# Truss-Power.net
KiCad netlist of a schematic drawn in EAGLE
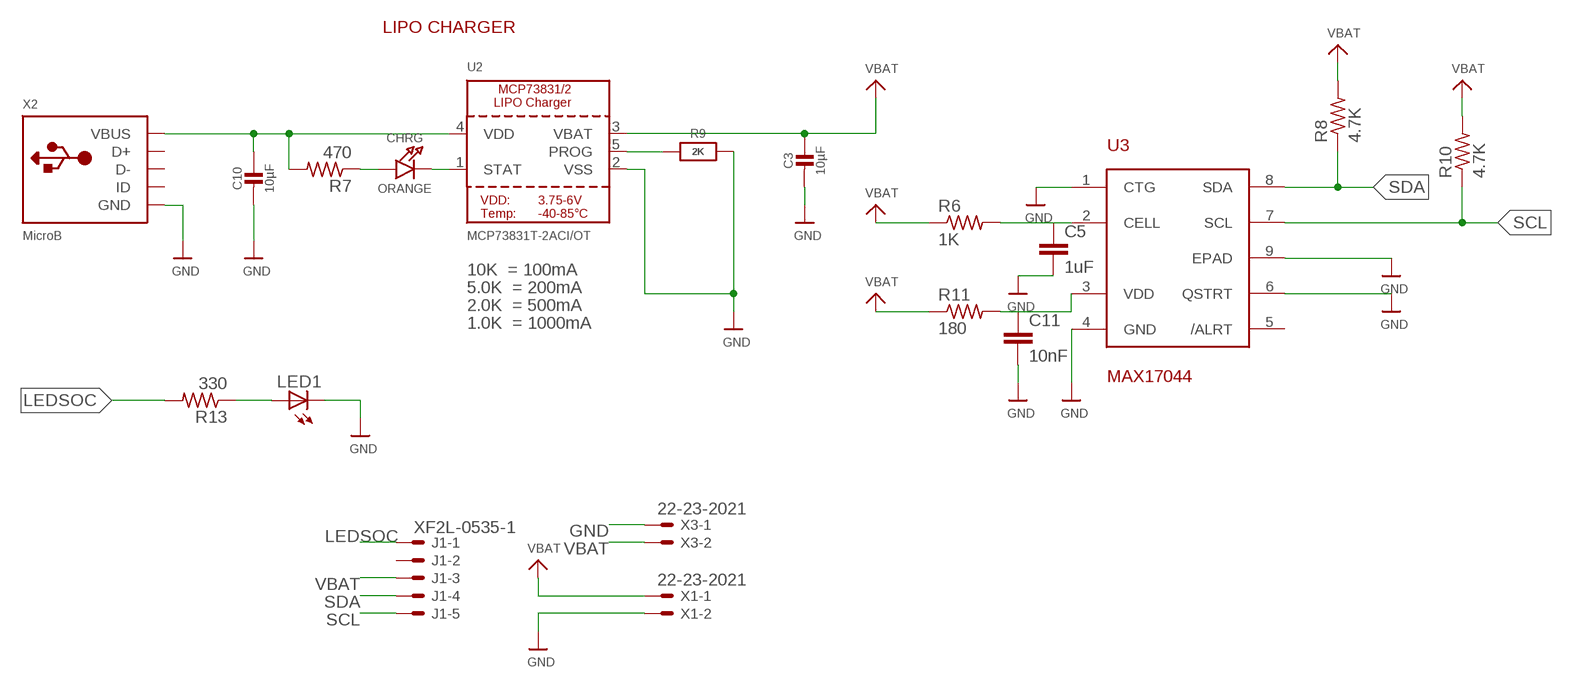
[diagram p0: schematic, sheet 1]

(export (version "E")
  (design (tool "Eeschema 10.0.6"))
  (components
    (comp (ref "C3")
      (value "10µF")
      (footprint "eagle-import:0805-NO")
      (libsource (lib "eagle-import") (part "CAP_CERAMIC0805-NOOUTLINE"))
    )
    (comp (ref "C5")
      (value "1uF")
      (footprint "eagle-import:C0603")
      (libsource (lib "eagle-import") (part "C-EUC0603"))
    )
    (comp (ref "C10")
      (value "10µF")
      (footprint "eagle-import:0805-NO")
      (libsource (lib "eagle-import") (part "CAP_CERAMIC0805-NOOUTLINE"))
    )
    (comp (ref "C11")
      (value "10nF")
      (footprint "eagle-import:C0603")
      (libsource (lib "eagle-import") (part "C-EUC0603"))
    )
    (comp (ref "CHRG")
      (value "ORANGE")
      (footprint "eagle-import:CHIPLED_0805_NOOUTLINE")
      (libsource (lib "eagle-import") (part "LED0805_NOOUTLINE"))
    )
    (comp (ref "J1")
      (value "XF2L-0535-1")
      (footprint "eagle-import:XF2L-0535-1")
      (fields (field (name "MPN") "XF2L-0535-1A"))
      (libsource (lib "eagle-import") (part "XF2-05?35-1L"))
    )
    (comp (ref "LED1")
      (value "LEDCHIP-LED0603")
      (footprint "eagle-import:CHIP-LED0603")
      (libsource (lib "eagle-import") (part "LEDCHIP-LED0603"))
    )
    (comp (ref "R6")
      (value "1K")
      (footprint "eagle-import:R0402")
      (libsource (lib "eagle-import") (part "R-US_R0402"))
    )
    (comp (ref "R7")
      (value "470")
      (footprint "eagle-import:R0402")
      (libsource (lib "eagle-import") (part "R-US_R0402"))
    )
    (comp (ref "R8")
      (value "4.7K")
      (footprint "eagle-import:R0402")
      (libsource (lib "eagle-import") (part "R-US_R0402"))
    )
    (comp (ref "R9")
      (value "2K")
      (footprint "eagle-import:0805-NO")
      (libsource (lib "eagle-import") (part "RESISTOR0805_NOOUTLINE"))
    )
    (comp (ref "R10")
      (value "4.7K")
      (footprint "eagle-import:R0402")
      (libsource (lib "eagle-import") (part "R-US_R0402"))
    )
    (comp (ref "R11")
      (value "180")
      (footprint "eagle-import:R0402")
      (libsource (lib "eagle-import") (part "R-US_R0402"))
    )
    (comp (ref "R13")
      (value "330")
      (footprint "eagle-import:R0402")
      (libsource (lib "eagle-import") (part "R-US_R0402"))
    )
    (comp (ref "U2")
      (value "MCP73831T-2ACI/OT")
      (footprint "eagle-import:SOT23-5")
      (libsource (lib "eagle-import") (part "MCP73831/2"))
    )
    (comp (ref "U3")
      (value "MAX17044")
      (footprint "eagle-import:TDFN")
      (libsource (lib "eagle-import") (part "MAX17044"))
    )
    (comp (ref "X1")
      (value "22-23-2021")
      (footprint "eagle-import:22-23-2021")
      (fields (field (name "MF") "MOLEX"))
      (libsource (lib "eagle-import") (part "con-molex_165_22-23-2021"))
    )
    (comp (ref "X2")
      (value "MicroB")
      (footprint "eagle-import:4UCONN_20329")
      (libsource (lib "eagle-import") (part "USBMICRO_20329"))
    )
    (comp (ref "X3")
      (value "22-23-2021")
      (footprint "eagle-import:22-23-2021")
      (fields (field (name "MF") "MOLEX"))
      (libsource (lib "eagle-import") (part "22-23-2021"))
    )
  )
  (nets
    (net (code "1") (name "GND") (class "Default")
      (node (ref "C10") (pin "2") (pinfunction "2_2") (pintype "passive"))
      (node (ref "C11") (pin "2") (pinfunction "2_2") (pintype "passive"))
      (node (ref "C3") (pin "2") (pinfunction "2_2") (pintype "passive"))
      (node (ref "C5") (pin "2") (pinfunction "2_2") (pintype "passive"))
      (node (ref "LED1") (pin "C") (pinfunction "C_C") (pintype "passive"))
      (node (ref "R9") (pin "2") (pinfunction "2_2") (pintype "passive"))
      (node (ref "U2") (pin "2") (pinfunction "VSS_2") (pintype "power_in"))
      (node (ref "U3") (pin "1") (pinfunction "CTG_1") (pintype "bidirectional"))
      (node (ref "U3") (pin "4") (pinfunction "GND_4") (pintype "bidirectional"))
      (node (ref "U3") (pin "6") (pinfunction "QSTRT_6") (pintype "bidirectional"))
      (node (ref "U3") (pin "9") (pinfunction "EPAD_9") (pintype "bidirectional"))
      (node (ref "X1") (pin "2") (pinfunction "S_2") (pintype "passive"))
      (node (ref "X2") (pin "BASE@1") (pinfunction "GND_BASE@1") (pintype "power_in"))
      (node (ref "X2") (pin "BASE@2") (pinfunction "GND_BASE@2") (pintype "power_in"))
      (node (ref "X2") (pin "GND") (pinfunction "GND_GND") (pintype "power_in"))
      (node (ref "X2") (pin "SPRT@1") (pinfunction "GND_SPRT@1") (pintype "power_in"))
      (node (ref "X2") (pin "SPRT@2") (pinfunction "GND_SPRT@2") (pintype "power_in"))
      (node (ref "X2") (pin "SPRT@3") (pinfunction "GND_SPRT@3") (pintype "power_in"))
      (node (ref "X2") (pin "SPRT@4") (pinfunction "GND_SPRT@4") (pintype "power_in"))
      (node (ref "X3") (pin "1") (pinfunction "S_1") (pintype "passive"))
    )
    (net (code "2") (name "LEDSOC") (class "Default")
      (node (ref "J1") (pin "1") (pinfunction "MSV_1") (pintype "passive"))
      (node (ref "R13") (pin "2") (pinfunction "2_2") (pintype "passive"))
    )
    (net (code "3") (name "Net-(CHRG-PadA)") (class "Default")
      (node (ref "CHRG") (pin "A") (pinfunction "A_A") (pintype "passive"))
      (node (ref "R7") (pin "1") (pinfunction "1_1") (pintype "passive"))
    )
    (net (code "4") (name "Net-(LED1-PadA)") (class "Default")
      (node (ref "LED1") (pin "A") (pinfunction "A_A") (pintype "passive"))
      (node (ref "R13") (pin "1") (pinfunction "1_1") (pintype "passive"))
    )
    (net (code "5") (name "Net-(U2-PROG)") (class "Default")
      (node (ref "R9") (pin "1") (pinfunction "1_1") (pintype "passive"))
      (node (ref "U2") (pin "5") (pinfunction "PROG_5") (pintype "input"))
    )
    (net (code "6") (name "Net-(U2-STAT)") (class "Default")
      (node (ref "CHRG") (pin "C") (pinfunction "C_C") (pintype "passive"))
      (node (ref "U2") (pin "1") (pinfunction "STAT_1") (pintype "output"))
    )
    (net (code "7") (name "Net-(U2-VDD)") (class "Default")
      (node (ref "C10") (pin "1") (pinfunction "1_1") (pintype "passive"))
      (node (ref "R7") (pin "2") (pinfunction "2_2") (pintype "passive"))
      (node (ref "U2") (pin "4") (pinfunction "VDD_4") (pintype "power_in"))
      (node (ref "X2") (pin "VBUS") (pinfunction "VBUS_VBUS") (pintype "power_in"))
    )
    (net (code "8") (name "Net-(U3-CELL)") (class "Default")
      (node (ref "C5") (pin "1") (pinfunction "1_1") (pintype "passive"))
      (node (ref "R6") (pin "2") (pinfunction "2_2") (pintype "passive"))
      (node (ref "U3") (pin "2") (pinfunction "CELL_2") (pintype "bidirectional"))
    )
    (net (code "9") (name "Net-(U3-VDD)") (class "Default")
      (node (ref "C11") (pin "1") (pinfunction "1_1") (pintype "passive"))
      (node (ref "R11") (pin "2") (pinfunction "2_2") (pintype "passive"))
      (node (ref "U3") (pin "3") (pinfunction "VDD_3") (pintype "bidirectional"))
    )
    (net (code "10") (name "SCL") (class "Default")
      (node (ref "J1") (pin "5") (pinfunction "MS_5") (pintype "passive"))
      (node (ref "R10") (pin "1") (pinfunction "1_1") (pintype "passive"))
      (node (ref "U3") (pin "7") (pinfunction "SCL_7") (pintype "bidirectional"))
    )
    (net (code "11") (name "SDA") (class "Default")
      (node (ref "J1") (pin "4") (pinfunction "MS_4") (pintype "passive"))
      (node (ref "R8") (pin "1") (pinfunction "1_1") (pintype "passive"))
      (node (ref "U3") (pin "8") (pinfunction "SDA_8") (pintype "bidirectional"))
    )
    (net (code "12") (name "VBAT") (class "Default")
      (node (ref "C3") (pin "1") (pinfunction "1_1") (pintype "passive"))
      (node (ref "J1") (pin "3") (pinfunction "MS_3") (pintype "passive"))
      (node (ref "R10") (pin "2") (pinfunction "2_2") (pintype "passive"))
      (node (ref "R11") (pin "1") (pinfunction "1_1") (pintype "passive"))
      (node (ref "R6") (pin "1") (pinfunction "1_1") (pintype "passive"))
      (node (ref "R8") (pin "2") (pinfunction "2_2") (pintype "passive"))
      (node (ref "U2") (pin "3") (pinfunction "VBAT_3") (pintype "power_in"))
      (node (ref "X1") (pin "1") (pinfunction "S_1") (pintype "passive"))
      (node (ref "X3") (pin "2") (pinfunction "S_2") (pintype "passive"))
    )
    (net (code "13") (name "unconnected-(J1B-MS-Pad2)") (class "Default")
      (node (ref "J1") (pin "2") (pinfunction "MS_2") (pintype "passive"))
    )
    (net (code "14") (name "unconnected-(U3-{slash}ALRT-Pad5)") (class "Default")
      (node (ref "U3") (pin "5") (pinfunction "/ALRT_5") (pintype "bidirectional"))
    )
    (net (code "15") (name "unconnected-(X2-PadD+)") (class "Default")
      (node (ref "X2") (pin "D+") (pinfunction "D+_D+") (pintype "bidirectional"))
    )
    (net (code "16") (name "unconnected-(X2-PadD-)") (class "Default")
      (node (ref "X2") (pin "D-") (pinfunction "D-_D-") (pintype "bidirectional"))
    )
    (net (code "17") (name "unconnected-(X2-PadID)") (class "Default")
      (node (ref "X2") (pin "ID") (pinfunction "ID_ID") (pintype "bidirectional"))
    )
  )
)
